# zxuno.net
KiCad netlist of a schematic drawn in Altium Designer
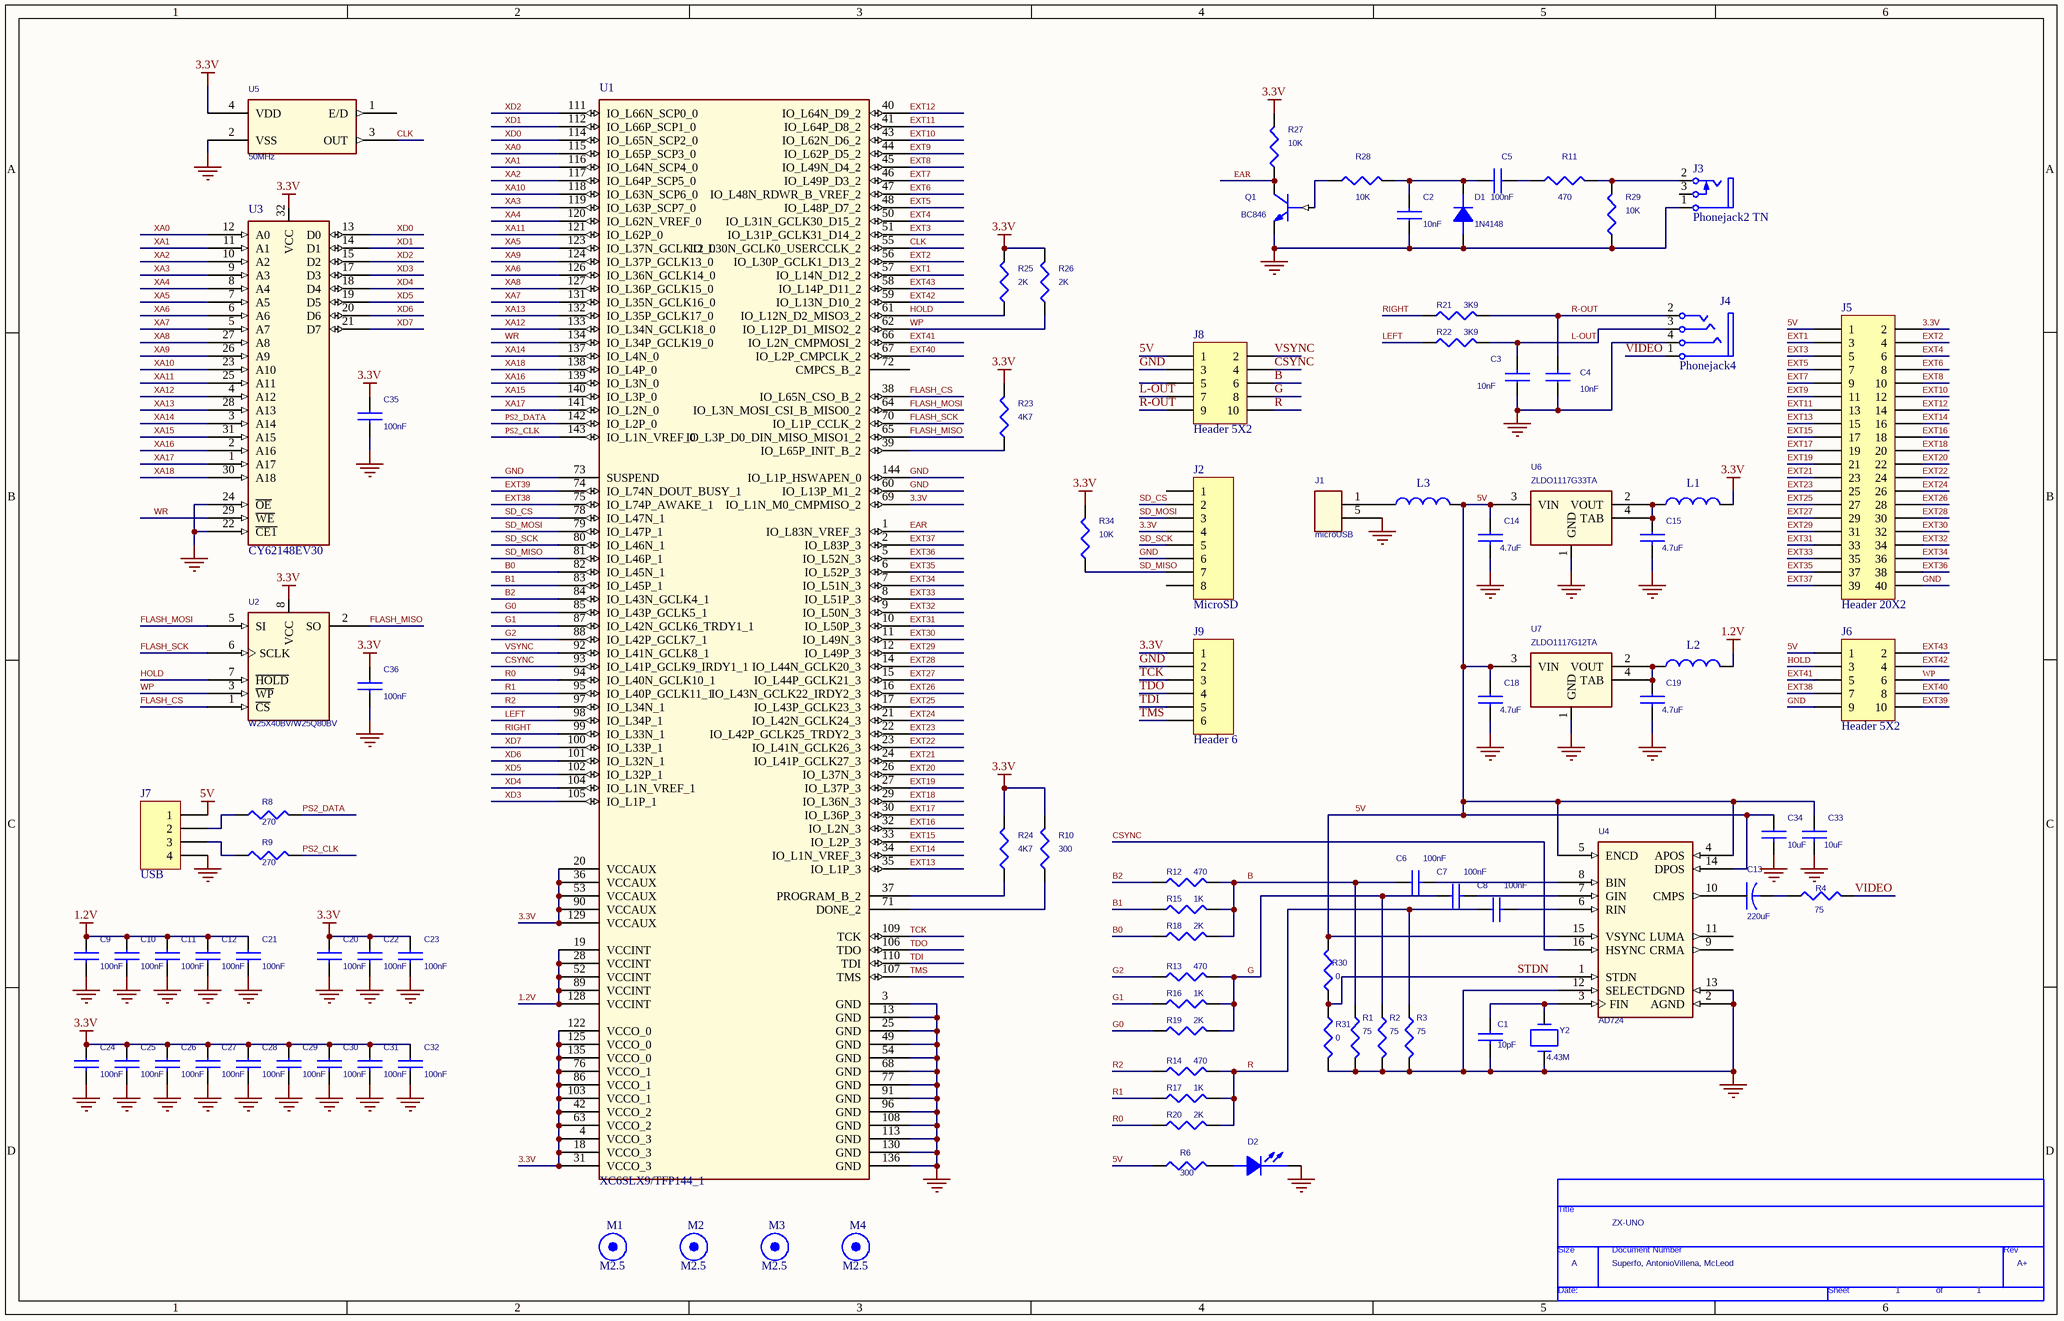
[diagram p0: zxuno.SchDoc]

(export (version "E")
  (design (tool "Eeschema 10.0.6"))
  (components
    (comp (ref "*")
      (value "TitleBlock0")
      (fields
        (field (name "PAGE COUNT") "1")
        (field (name "PAGE NUMBER") "1")
        (field (name "PAGE SIZE") "A")
        (field (name "TITLE") "ZX-UNO")
        (field (name "REVCODE") "A+")
        (field (name "DOC") "Superfo, AntonioVillena, McLeod")
      )
      (libsource (lib "*") (part "TitleBlock0"))
    )
    (comp (ref "C1") (value "10pF") (libsource (lib "*") (part "CAP NP_Dup1")))
    (comp (ref "C2") (value "10nF") (libsource (lib "*") (part "CAP NP_Dup1")))
    (comp (ref "C3") (value "10nF") (libsource (lib "*") (part "CAP NP_Dup1")))
    (comp (ref "C4") (value "10nF") (libsource (lib "*") (part "CAP NP_Dup1")))
    (comp (ref "C5") (value "100nF") (libsource (lib "*") (part "CAP NP_Dup1")))
    (comp (ref "C6") (value "100nF") (libsource (lib "*") (part "CAP NP_Dup1")))
    (comp (ref "C7") (value "100nF") (libsource (lib "*") (part "CAP NP_Dup1")))
    (comp (ref "C8") (value "100nF") (libsource (lib "*") (part "CAP NP_Dup1")))
    (comp (ref "C9") (value "100nF") (libsource (lib "*") (part "CAP NP")))
    (comp (ref "C10") (value "100nF") (libsource (lib "*") (part "CAP NP")))
    (comp (ref "C11") (value "100nF") (libsource (lib "*") (part "CAP NP")))
    (comp (ref "C12") (value "100nF") (libsource (lib "*") (part "CAP NP")))
    (comp (ref "C13") (value "220uF") (libsource (lib "*") (part "CAP")))
    (comp (ref "C14") (value "4.7uF") (libsource (lib "*") (part "CAP NP")))
    (comp (ref "C15") (value "4.7uF") (libsource (lib "*") (part "CAP NP")))
    (comp (ref "C18") (value "4.7uF") (libsource (lib "*") (part "CAP NP")))
    (comp (ref "C19") (value "4.7uF") (libsource (lib "*") (part "CAP NP")))
    (comp (ref "C20") (value "100nF") (libsource (lib "*") (part "CAP NP")))
    (comp (ref "C21") (value "100nF") (libsource (lib "*") (part "CAP NP")))
    (comp (ref "C22") (value "100nF") (libsource (lib "*") (part "CAP NP")))
    (comp (ref "C23") (value "100nF") (libsource (lib "*") (part "CAP NP")))
    (comp (ref "C24") (value "100nF") (libsource (lib "*") (part "CAP NP")))
    (comp (ref "C25") (value "100nF") (libsource (lib "*") (part "CAP NP")))
    (comp (ref "C26") (value "100nF") (libsource (lib "*") (part "CAP NP")))
    (comp (ref "C27") (value "100nF") (libsource (lib "*") (part "CAP NP")))
    (comp (ref "C28") (value "100nF") (libsource (lib "*") (part "CAP NP")))
    (comp (ref "C29") (value "100nF") (libsource (lib "*") (part "CAP NP")))
    (comp (ref "C30") (value "100nF") (libsource (lib "*") (part "CAP NP")))
    (comp (ref "C31") (value "100nF") (libsource (lib "*") (part "CAP NP")))
    (comp (ref "C32") (value "100nF") (libsource (lib "*") (part "CAP NP")))
    (comp (ref "C33") (value "10uF") (libsource (lib "*") (part "CAP NP")))
    (comp (ref "C34") (value "10uF") (libsource (lib "*") (part "CAP NP")))
    (comp (ref "C35") (value "100nF") (libsource (lib "*") (part "CAP NP")))
    (comp (ref "C36") (value "100nF") (libsource (lib "*") (part "CAP NP")))
    (comp (ref "D1") (value "1N4148") (libsource (lib "*") (part "DIODE")))
    (comp (ref "D2") (value "LED") (libsource (lib "*") (part "LED")))
    (comp (ref "J1") (value "microUSB") (libsource (lib "*") (part "CON2_0")))
    (comp (ref "J2")
      (value "MicroSD")
      (footprint "SD HR1941CT-ND")
      (description "Header, 8-Pin")
      (fields (field (name "PUBLISHER") "Altium Limited"))
      (libsource (lib "Miscellaneous Connectors") (part "Header 8"))
    )
    (comp (ref "J3")
      (value "Phonejack2 TN")
      (footprint "AUDIO  JACK MJ-2523-SMT")
      (description "Jack Socket, 3.5mm, Thru-Hole, Vertical, 2-Conductor with Tip closed")
      (fields (field (name "PUBLISHER") "Altium Limited"))
      (libsource (lib "Retro Computer") (part "Phonejack2 TN"))
    )
    (comp (ref "J4")
      (value "Phonejack4")
      (footprint "AUDIO  JACK SJ-43514-SMT")
      (description "Jack Socket, 3.5mm, Thru-Hole, Right Angle, 4-Conductor")
      (fields (field (name "PUBLISHER") "Altium Limited"))
      (libsource (lib "Retro Computer") (part "Phonejack4"))
    )
    (comp (ref "J5")
      (value "Header 20X2")
      (footprint "HDR2X20")
      (description "Header, 20-Pin, Dual row")
      (fields (field (name "PUBLISHER") "Altium Limited"))
      (libsource (lib "Miscellaneous Connectors") (part "Header 20X2"))
    )
    (comp (ref "J6")
      (value "Header 5X2")
      (footprint "HDR2X5")
      (description "Header, 5-Pin, Dual row")
      (fields (field (name "PUBLISHER") "Altium Limited"))
      (libsource (lib "Miscellaneous Connectors") (part "Header 5X2"))
    )
    (comp (ref "J7")
      (value "USB")
      (footprint "USB A")
      (description "Header, 4-Pin")
      (fields (field (name "PUBLISHER") "Altium Limited"))
      (libsource (lib "Miscellaneous Connectors") (part "Header 4"))
    )
    (comp (ref "J8")
      (value "Header 5X2")
      (footprint "HDR2X5")
      (description "Header, 5-Pin, Dual row")
      (fields (field (name "PUBLISHER") "Altium Limited"))
      (libsource (lib "Miscellaneous Connectors") (part "Header 5X2"))
    )
    (comp (ref "J9")
      (value "Header 6")
      (footprint "HDR1X6")
      (description "Header, 6-Pin")
      (fields (field (name "PUBLISHER") "Altium Limited"))
      (libsource (lib "Miscellaneous Connectors") (part "Header 6"))
    )
    (comp (ref "L1")
      (value "Inductor")
      (footprint "SM/L_0805")
      (fields (field (name "PUBLISHER") "Altium Limited"))
      (libsource (lib "Miscellaneous Devices") (part "Inductor"))
    )
    (comp (ref "L2")
      (value "Inductor")
      (footprint "SM/L_0805")
      (fields (field (name "PUBLISHER") "Altium Limited"))
      (libsource (lib "Miscellaneous Devices") (part "Inductor"))
    )
    (comp (ref "L3")
      (value "Inductor")
      (footprint "SM/L_0805")
      (fields (field (name "PUBLISHER") "Altium Limited"))
      (libsource (lib "Miscellaneous Devices") (part "Inductor"))
    )
    (comp (ref "M1") (value "M2.5") (footprint "M2.5") (libsource (lib "Misc Devices 2") (part "M2.5")))
    (comp (ref "M2") (value "M2.5") (footprint "M2.5") (libsource (lib "Misc Devices 2") (part "M2.5")))
    (comp (ref "M3") (value "M2.5") (footprint "M2.5") (libsource (lib "Misc Devices 2") (part "M2.5")))
    (comp (ref "M4") (value "M2.5") (footprint "M2.5") (libsource (lib "Misc Devices 2") (part "M2.5")))
    (comp (ref "Q1") (value "BC846") (libsource (lib "*") (part "BC547")))
    (comp (ref "R1") (value "75") (libsource (lib "*") (part "R")))
    (comp (ref "R2") (value "75") (libsource (lib "*") (part "R")))
    (comp (ref "R3") (value "75") (libsource (lib "*") (part "R")))
    (comp (ref "R4") (value "75") (libsource (lib "*") (part "R")))
    (comp (ref "R6") (value "300") (libsource (lib "*") (part "R")))
    (comp (ref "R8") (value "270") (libsource (lib "*") (part "R")))
    (comp (ref "R9") (value "270") (libsource (lib "*") (part "R")))
    (comp (ref "R10") (value "300") (libsource (lib "*") (part "R")))
    (comp (ref "R11") (value "470") (libsource (lib "*") (part "R")))
    (comp (ref "R12") (value "470") (libsource (lib "*") (part "R")))
    (comp (ref "R13") (value "470") (libsource (lib "*") (part "R")))
    (comp (ref "R14") (value "470") (libsource (lib "*") (part "R")))
    (comp (ref "R15") (value "1K") (libsource (lib "*") (part "R")))
    (comp (ref "R16") (value "1K") (libsource (lib "*") (part "R")))
    (comp (ref "R17") (value "1K") (libsource (lib "*") (part "R")))
    (comp (ref "R18") (value "2K") (libsource (lib "*") (part "R")))
    (comp (ref "R19") (value "2K") (libsource (lib "*") (part "R")))
    (comp (ref "R20") (value "2K") (libsource (lib "*") (part "R")))
    (comp (ref "R21") (value "3K9") (libsource (lib "*") (part "R")))
    (comp (ref "R22") (value "3K9") (libsource (lib "*") (part "R")))
    (comp (ref "R23") (value "4K7") (libsource (lib "*") (part "R")))
    (comp (ref "R24") (value "4K7") (libsource (lib "*") (part "R")))
    (comp (ref "R25") (value "2K") (libsource (lib "*") (part "R")))
    (comp (ref "R26") (value "2K") (libsource (lib "*") (part "R")))
    (comp (ref "R27") (value "10K") (libsource (lib "*") (part "R")))
    (comp (ref "R28") (value "10K") (libsource (lib "*") (part "R")))
    (comp (ref "R29") (value "10K") (libsource (lib "*") (part "R")))
    (comp (ref "R30") (value "0") (libsource (lib "*") (part "R")))
    (comp (ref "R31") (value "0") (libsource (lib "*") (part "R")))
    (comp (ref "R34") (value "10K") (libsource (lib "*") (part "R")))
    (comp (ref "U1")
      (value "XC6SLX9/TFP144_1")
      (libsource (lib "ZX_UNO_0_13_Library") (part "XC6SLX9/TFP144_1"))
    )
    (comp (ref "U2") (value "W25X40BV/W25Q80BV") (libsource (lib "*") (part "AT45DB011/SOIC_3")))
    (comp (ref "U3") (value "CY62148EV30") (libsource (lib "ZX_UNO_0_13_Library") (part "CY62128/SOIC_3")))
    (comp (ref "U4") (value "AD724") (libsource (lib "*") (part "AD724")))
    (comp (ref "U5") (value "50MHz") (libsource (lib "*") (part "CS-403/TO_0")))
    (comp (ref "U6")
      (value "ZLDO1117G33TA")
      (footprint "SM/SOT223")
      (libsource (lib "*") (part "REGULATOR-1_0"))
    )
    (comp (ref "U7")
      (value "ZLDO1117G12TA")
      (footprint "SM/SOT223")
      (libsource (lib "*") (part "REGULATOR-1_0"))
    )
    (comp (ref "Y2") (value "4.43M") (libsource (lib "*") (part "CRYSTAL")))
  )
  (nets
    (net (code "1") (name "/B") (class "Default")
      (node (ref "C6") (pin "1") (pinfunction "1_1") (pintype "passive"))
      (node (ref "J8") (pin "6") (pinfunction "6_6") (pintype "passive"))
      (node (ref "R1") (pin "1") (pinfunction "1_1") (pintype "passive"))
      (node (ref "R12") (pin "2") (pinfunction "2_2") (pintype "passive"))
      (node (ref "R15") (pin "2") (pinfunction "2_2") (pintype "passive"))
      (node (ref "R18") (pin "2") (pinfunction "2_2") (pintype "passive"))
    )
    (net (code "2") (name "/B0") (class "Default")
      (node (ref "R18") (pin "1") (pinfunction "1_1") (pintype "passive"))
      (node (ref "U1") (pin "82") (pinfunction "IO_L45N_1_82") (pintype "bidirectional"))
    )
    (net (code "3") (name "/B1") (class "Default")
      (node (ref "R15") (pin "1") (pinfunction "1_1") (pintype "passive"))
      (node (ref "U1") (pin "83") (pinfunction "IO_L45P_1_83") (pintype "bidirectional"))
    )
    (net (code "4") (name "/B2") (class "Default")
      (node (ref "R12") (pin "1") (pinfunction "1_1") (pintype "passive"))
      (node (ref "U1") (pin "84") (pinfunction "IO_L43N_GCLK4_1_84") (pintype "bidirectional"))
    )
    (net (code "5") (name "/CLK") (class "Default")
      (node (ref "U1") (pin "55") (pinfunction "IO_L30N_GCLK0_USERCCLK_2_55") (pintype "bidirectional"))
      (node (ref "U5") (pin "3") (pinfunction "OUT_3") (pintype "output"))
    )
    (net (code "6") (name "/CSYNC") (class "Default")
      (node (ref "J8") (pin "4") (pinfunction "4_4") (pintype "passive"))
      (node (ref "U1") (pin "93") (pinfunction "IO_L41P_GCLK9_IRDY1_1_93") (pintype "bidirectional"))
      (node (ref "U4") (pin "16") (pinfunction "HSYNC_16") (pintype "input"))
    )
    (net (code "7") (name "/EAR") (class "Default")
      (node (ref "Q1") (pin "1") (pinfunction "COLLECTOR_1") (pintype "passive"))
      (node (ref "R27") (pin "2") (pinfunction "2_2") (pintype "passive"))
      (node (ref "U1") (pin "1") (pinfunction "IO_L83N_VREF_3_1") (pintype "bidirectional"))
    )
    (net (code "8") (name "/EXT1") (class "Default")
      (node (ref "J5") (pin "3") (pinfunction "3_3") (pintype "passive"))
      (node (ref "U1") (pin "57") (pinfunction "IO_L14N_D12_2_57") (pintype "bidirectional"))
    )
    (net (code "9") (name "/EXT2") (class "Default")
      (node (ref "J5") (pin "4") (pinfunction "4_4") (pintype "passive"))
      (node (ref "U1") (pin "56") (pinfunction "IO_L30P_GCLK1_D13_2_56") (pintype "bidirectional"))
    )
    (net (code "10") (name "/EXT3") (class "Default")
      (node (ref "J5") (pin "5") (pinfunction "5_5") (pintype "passive"))
      (node (ref "U1") (pin "51") (pinfunction "IO_L31P_GCLK31_D14_2_51") (pintype "bidirectional"))
    )
    (net (code "11") (name "/EXT4") (class "Default")
      (node (ref "J5") (pin "6") (pinfunction "6_6") (pintype "passive"))
      (node (ref "U1") (pin "50") (pinfunction "IO_L31N_GCLK30_D15_2_50") (pintype "bidirectional"))
    )
    (net (code "12") (name "/EXT5") (class "Default")
      (node (ref "J5") (pin "7") (pinfunction "7_7") (pintype "passive"))
      (node (ref "U1") (pin "48") (pinfunction "IO_L48P_D7_2_48") (pintype "bidirectional"))
    )
    (net (code "13") (name "/EXT6") (class "Default")
      (node (ref "J5") (pin "8") (pinfunction "8_8") (pintype "passive"))
      (node (ref "U1") (pin "47") (pinfunction "IO_L48N_RDWR_B_VREF_2_47") (pintype "bidirectional"))
    )
    (net (code "14") (name "/EXT7") (class "Default")
      (node (ref "J5") (pin "9") (pinfunction "9_9") (pintype "passive"))
      (node (ref "U1") (pin "46") (pinfunction "IO_L49P_D3_2_46") (pintype "bidirectional"))
    )
    (net (code "15") (name "/EXT8") (class "Default")
      (node (ref "J5") (pin "10") (pinfunction "10_10") (pintype "passive"))
      (node (ref "U1") (pin "45") (pinfunction "IO_L49N_D4_2_45") (pintype "bidirectional"))
    )
    (net (code "16") (name "/EXT9") (class "Default")
      (node (ref "J5") (pin "11") (pinfunction "11_11") (pintype "passive"))
      (node (ref "U1") (pin "44") (pinfunction "IO_L62P_D5_2_44") (pintype "bidirectional"))
    )
    (net (code "17") (name "/EXT10") (class "Default")
      (node (ref "J5") (pin "12") (pinfunction "12_12") (pintype "passive"))
      (node (ref "U1") (pin "43") (pinfunction "IO_L62N_D6_2_43") (pintype "bidirectional"))
    )
    (net (code "18") (name "/EXT11") (class "Default")
      (node (ref "J5") (pin "13") (pinfunction "13_13") (pintype "passive"))
      (node (ref "U1") (pin "41") (pinfunction "IO_L64P_D8_2_41") (pintype "bidirectional"))
    )
    (net (code "19") (name "/EXT12") (class "Default")
      (node (ref "J5") (pin "14") (pinfunction "14_14") (pintype "passive"))
      (node (ref "U1") (pin "40") (pinfunction "IO_L64N_D9_2_40") (pintype "bidirectional"))
    )
    (net (code "20") (name "/EXT13") (class "Default")
      (node (ref "J5") (pin "15") (pinfunction "15_15") (pintype "passive"))
      (node (ref "U1") (pin "35") (pinfunction "IO_L1P_3_35") (pintype "bidirectional"))
    )
    (net (code "21") (name "/EXT14") (class "Default")
      (node (ref "J5") (pin "16") (pinfunction "16_16") (pintype "passive"))
      (node (ref "U1") (pin "34") (pinfunction "IO_L1N_VREF_3_34") (pintype "bidirectional"))
    )
    (net (code "22") (name "/EXT15") (class "Default")
      (node (ref "J5") (pin "17") (pinfunction "17_17") (pintype "passive"))
      (node (ref "U1") (pin "33") (pinfunction "IO_L2P_3_33") (pintype "bidirectional"))
    )
    (net (code "23") (name "/EXT16") (class "Default")
      (node (ref "J5") (pin "18") (pinfunction "18_18") (pintype "passive"))
      (node (ref "U1") (pin "32") (pinfunction "IO_L2N_3_32") (pintype "bidirectional"))
    )
    (net (code "24") (name "/EXT17") (class "Default")
      (node (ref "J5") (pin "19") (pinfunction "19_19") (pintype "passive"))
      (node (ref "U1") (pin "30") (pinfunction "IO_L36P_3_30") (pintype "bidirectional"))
    )
    (net (code "25") (name "/EXT18") (class "Default")
      (node (ref "J5") (pin "20") (pinfunction "20_20") (pintype "passive"))
      (node (ref "U1") (pin "29") (pinfunction "IO_L36N_3_29") (pintype "bidirectional"))
    )
    (net (code "26") (name "/EXT19") (class "Default")
      (node (ref "J5") (pin "21") (pinfunction "21_21") (pintype "passive"))
      (node (ref "U1") (pin "27") (pinfunction "IO_L37P_3_27") (pintype "bidirectional"))
    )
    (net (code "27") (name "/EXT20") (class "Default")
      (node (ref "J5") (pin "22") (pinfunction "22_22") (pintype "passive"))
      (node (ref "U1") (pin "26") (pinfunction "IO_L37N_3_26") (pintype "bidirectional"))
    )
    (net (code "28") (name "/EXT21") (class "Default")
      (node (ref "J5") (pin "23") (pinfunction "23_23") (pintype "passive"))
      (node (ref "U1") (pin "24") (pinfunction "IO_L41P_GCLK27_3_24") (pintype "bidirectional"))
    )
    (net (code "29") (name "/EXT22") (class "Default")
      (node (ref "J5") (pin "24") (pinfunction "24_24") (pintype "passive"))
      (node (ref "U1") (pin "23") (pinfunction "IO_L41N_GCLK26_3_23") (pintype "bidirectional"))
    )
    (net (code "30") (name "/EXT23") (class "Default")
      (node (ref "J5") (pin "25") (pinfunction "25_25") (pintype "passive"))
      (node (ref "U1") (pin "22") (pinfunction "IO_L42P_GCLK25_TRDY2_3_22") (pintype "bidirectional"))
    )
    (net (code "31") (name "/EXT24") (class "Default")
      (node (ref "J5") (pin "26") (pinfunction "26_26") (pintype "passive"))
      (node (ref "U1") (pin "21") (pinfunction "IO_L42N_GCLK24_3_21") (pintype "bidirectional"))
    )
    (net (code "32") (name "/EXT25") (class "Default")
      (node (ref "J5") (pin "27") (pinfunction "27_27") (pintype "passive"))
      (node (ref "U1") (pin "17") (pinfunction "IO_L43P_GCLK23_3_17") (pintype "bidirectional"))
    )
    (net (code "33") (name "/EXT26") (class "Default")
      (node (ref "J5") (pin "28") (pinfunction "28_28") (pintype "passive"))
      (node (ref "U1") (pin "16") (pinfunction "IO_L43N_GCLK22_IRDY2_3_16") (pintype "bidirectional"))
    )
    (net (code "34") (name "/EXT27") (class "Default")
      (node (ref "J5") (pin "29") (pinfunction "29_29") (pintype "passive"))
      (node (ref "U1") (pin "15") (pinfunction "IO_L44P_GCLK21_3_15") (pintype "bidirectional"))
    )
    (net (code "35") (name "/EXT28") (class "Default")
      (node (ref "J5") (pin "30") (pinfunction "30_30") (pintype "passive"))
      (node (ref "U1") (pin "14") (pinfunction "IO_L44N_GCLK20_3_14") (pintype "bidirectional"))
    )
    (net (code "36") (name "/EXT29") (class "Default")
      (node (ref "J5") (pin "31") (pinfunction "31_31") (pintype "passive"))
      (node (ref "U1") (pin "12") (pinfunction "IO_L49P_3_12") (pintype "bidirectional"))
    )
    (net (code "37") (name "/EXT30") (class "Default")
      (node (ref "J5") (pin "32") (pinfunction "32_32") (pintype "passive"))
      (node (ref "U1") (pin "11") (pinfunction "IO_L49N_3_11") (pintype "bidirectional"))
    )
    (net (code "38") (name "/EXT31") (class "Default")
      (node (ref "J5") (pin "33") (pinfunction "33_33") (pintype "passive"))
      (node (ref "U1") (pin "10") (pinfunction "IO_L50P_3_10") (pintype "bidirectional"))
    )
    (net (code "39") (name "/EXT32") (class "Default")
      (node (ref "J5") (pin "34") (pinfunction "34_34") (pintype "passive"))
      (node (ref "U1") (pin "9") (pinfunction "IO_L50N_3_9") (pintype "bidirectional"))
    )
    (net (code "40") (name "/EXT33") (class "Default")
      (node (ref "J5") (pin "35") (pinfunction "35_35") (pintype "passive"))
      (node (ref "U1") (pin "8") (pinfunction "IO_L51P_3_8") (pintype "bidirectional"))
    )
    (net (code "41") (name "/EXT34") (class "Default")
      (node (ref "J5") (pin "36") (pinfunction "36_36") (pintype "passive"))
      (node (ref "U1") (pin "7") (pinfunction "IO_L51N_3_7") (pintype "bidirectional"))
    )
    (net (code "42") (name "/EXT35") (class "Default")
      (node (ref "J5") (pin "37") (pinfunction "37_37") (pintype "passive"))
      (node (ref "U1") (pin "6") (pinfunction "IO_L52P_3_6") (pintype "bidirectional"))
    )
    (net (code "43") (name "/EXT36") (class "Default")
      (node (ref "J5") (pin "38") (pinfunction "38_38") (pintype "passive"))
      (node (ref "U1") (pin "5") (pinfunction "IO_L52N_3_5") (pintype "bidirectional"))
    )
    (net (code "44") (name "/EXT37") (class "Default")
      (node (ref "J5") (pin "39") (pinfunction "39_39") (pintype "passive"))
      (node (ref "U1") (pin "2") (pinfunction "IO_L83P_3_2") (pintype "bidirectional"))
    )
    (net (code "45") (name "/EXT38") (class "Default")
      (node (ref "J6") (pin "7") (pinfunction "7_7") (pintype "passive"))
      (node (ref "U1") (pin "75") (pinfunction "IO_L74P_AWAKE_1_75") (pintype "bidirectional"))
    )
    (net (code "46") (name "/EXT39") (class "Default")
      (node (ref "J6") (pin "10") (pinfunction "10_10") (pintype "passive"))
      (node (ref "U1") (pin "74") (pinfunction "IO_L74N_DOUT_BUSY_1_74") (pintype "bidirectional"))
    )
    (net (code "47") (name "/EXT40") (class "Default")
      (node (ref "J6") (pin "8") (pinfunction "8_8") (pintype "passive"))
      (node (ref "U1") (pin "67") (pinfunction "IO_L2P_CMPCLK_2_67") (pintype "bidirectional"))
    )
    (net (code "48") (name "/EXT41") (class "Default")
      (node (ref "J6") (pin "5") (pinfunction "5_5") (pintype "passive"))
      (node (ref "U1") (pin "66") (pinfunction "IO_L2N_CMPMOSI_2_66") (pintype "bidirectional"))
    )
    (net (code "49") (name "/EXT42") (class "Default")
      (node (ref "J6") (pin "4") (pinfunction "4_4") (pintype "passive"))
      (node (ref "U1") (pin "59") (pinfunction "IO_L13N_D10_2_59") (pintype "bidirectional"))
    )
    (net (code "50") (name "/EXT43") (class "Default")
      (node (ref "J6") (pin "2") (pinfunction "2_2") (pintype "passive"))
      (node (ref "U1") (pin "58") (pinfunction "IO_L14P_D11_2_58") (pintype "bidirectional"))
    )
    (net (code "51") (name "/FLASH_CS") (class "Default")
      (node (ref "U1") (pin "38") (pinfunction "IO_L65N_CSO_B_2_38") (pintype "bidirectional"))
      (node (ref "U2") (pin "1") (pinfunction "~{CS}_1") (pintype "input"))
    )
    (net (code "52") (name "/FLASH_MISO") (class "Default")
      (node (ref "U1") (pin "65") (pinfunction "IO_L3P_D0_DIN_MISO_MISO1_2_65") (pintype "bidirectional"))
      (node (ref "U2") (pin "2") (pinfunction "SO_2") (pintype "tri_state"))
    )
    (net (code "53") (name "/FLASH_MOSI") (class "Default")
      (node (ref "U1") (pin "64") (pinfunction "IO_L3N_MOSI_CSI_B_MISO0_2_64") (pintype "bidirectional"))
      (node (ref "U2") (pin "5") (pinfunction "SI_5") (pintype "input"))
    )
    (net (code "54") (name "/FLASH_SCK") (class "Default")
      (node (ref "U1") (pin "70") (pinfunction "IO_L1P_CCLK_2_70") (pintype "bidirectional"))
      (node (ref "U2") (pin "6") (pinfunction "SCLK_6") (pintype "input"))
    )
    (net (code "55") (name "/G") (class "Default")
      (node (ref "C7") (pin "1") (pinfunction "1_1") (pintype "passive"))
      (node (ref "J8") (pin "8") (pinfunction "8_8") (pintype "passive"))
      (node (ref "R13") (pin "2") (pinfunction "2_2") (pintype "passive"))
      (node (ref "R16") (pin "2") (pinfunction "2_2") (pintype "passive"))
      (node (ref "R19") (pin "2") (pinfunction "2_2") (pintype "passive"))
      (node (ref "R2") (pin "1") (pinfunction "1_1") (pintype "passive"))
    )
    (net (code "56") (name "/G0") (class "Default")
      (node (ref "R19") (pin "1") (pinfunction "1_1") (pintype "passive"))
      (node (ref "U1") (pin "85") (pinfunction "IO_L43P_GCLK5_1_85") (pintype "bidirectional"))
    )
    (net (code "57") (name "/G1") (class "Default")
      (node (ref "R16") (pin "1") (pinfunction "1_1") (pintype "passive"))
      (node (ref "U1") (pin "87") (pinfunction "IO_L42N_GCLK6_TRDY1_1_87") (pintype "bidirectional"))
    )
    (net (code "58") (name "/G2") (class "Default")
      (node (ref "R13") (pin "1") (pinfunction "1_1") (pintype "passive"))
      (node (ref "U1") (pin "88") (pinfunction "IO_L42P_GCLK7_1_88") (pintype "bidirectional"))
    )
    (net (code "59") (name "/HOLD") (class "Default")
      (node (ref "J6") (pin "3") (pinfunction "3_3") (pintype "passive"))
      (node (ref "R25") (pin "1") (pinfunction "1_1") (pintype "passive"))
      (node (ref "U1") (pin "61") (pinfunction "IO_L12N_D2_MISO3_2_61") (pintype "bidirectional"))
      (node (ref "U2") (pin "7") (pinfunction "~{HOLD}_7") (pintype "input"))
    )
    (net (code "60") (name "/L-OUT") (class "Default")
      (node (ref "C3") (pin "2") (pinfunction "2_2") (pintype "passive"))
      (node (ref "J4") (pin "3") (pinfunction "RN_3") (pintype "passive"))
      (node (ref "J8") (pin "7") (pinfunction "7_7") (pintype "passive"))
      (node (ref "R22") (pin "2") (pinfunction "2_2") (pintype "passive"))
    )
    (net (code "61") (name "/LEFT") (class "Default")
      (node (ref "R22") (pin "1") (pinfunction "1_1") (pintype "passive"))
      (node (ref "U1") (pin "98") (pinfunction "IO_L34P_1_98") (pintype "bidirectional"))
    )
    (net (code "62") (name "/PS2_CLK") (class "Default")
      (node (ref "R9") (pin "2") (pinfunction "2_2") (pintype "passive"))
      (node (ref "U1") (pin "143") (pinfunction "IO_L1N_VREF_0_143") (pintype "bidirectional"))
    )
    (net (code "63") (name "/PS2_DATA") (class "Default")
      (node (ref "R8") (pin "2") (pinfunction "2_2") (pintype "passive"))
      (node (ref "U1") (pin "142") (pinfunction "IO_L2P_0_142") (pintype "bidirectional"))
    )
    (net (code "64") (name "/R") (class "Default")
      (node (ref "C8") (pin "1") (pinfunction "1_1") (pintype "passive"))
      (node (ref "J8") (pin "10") (pinfunction "10_10") (pintype "passive"))
      (node (ref "R14") (pin "2") (pinfunction "2_2") (pintype "passive"))
      (node (ref "R17") (pin "2") (pinfunction "2_2") (pintype "passive"))
      (node (ref "R20") (pin "2") (pinfunction "2_2") (pintype "passive"))
      (node (ref "R3") (pin "1") (pinfunction "1_1") (pintype "passive"))
    )
    (net (code "65") (name "/R-OUT") (class "Default")
      (node (ref "C4") (pin "2") (pinfunction "2_2") (pintype "passive"))
      (node (ref "J4") (pin "2") (pinfunction "T_2") (pintype "passive"))
      (node (ref "J8") (pin "9") (pinfunction "9_9") (pintype "passive"))
      (node (ref "R21") (pin "2") (pinfunction "2_2") (pintype "passive"))
    )
    (net (code "66") (name "/R0") (class "Default")
      (node (ref "R20") (pin "1") (pinfunction "1_1") (pintype "passive"))
      (node (ref "U1") (pin "94") (pinfunction "IO_L40N_GCLK10_1_94") (pintype "bidirectional"))
    )
    (net (code "67") (name "/R1") (class "Default")
      (node (ref "R17") (pin "1") (pinfunction "1_1") (pintype "passive"))
      (node (ref "U1") (pin "95") (pinfunction "IO_L40P_GCLK11_1_95") (pintype "bidirectional"))
    )
    (net (code "68") (name "/R2") (class "Default")
      (node (ref "R14") (pin "1") (pinfunction "1_1") (pintype "passive"))
      (node (ref "U1") (pin "97") (pinfunction "IO_L34N_1_97") (pintype "bidirectional"))
    )
    (net (code "69") (name "/RIGHT") (class "Default")
      (node (ref "R21") (pin "1") (pinfunction "1_1") (pintype "passive"))
      (node (ref "U1") (pin "99") (pinfunction "IO_L33N_1_99") (pintype "bidirectional"))
    )
    (net (code "70") (name "/SD_CS") (class "Default")
      (node (ref "J2") (pin "2") (pinfunction "2_2") (pintype "passive"))
      (node (ref "U1") (pin "78") (pinfunction "IO_L47N_1_78") (pintype "bidirectional"))
    )
    (net (code "71") (name "/SD_MISO") (class "Default")
      (node (ref "J2") (pin "7") (pinfunction "7_7") (pintype "passive"))
      (node (ref "R34") (pin "1") (pinfunction "1_1") (pintype "passive"))
      (node (ref "U1") (pin "81") (pinfunction "IO_L46P_1_81") (pintype "bidirectional"))
    )
    (net (code "72") (name "/SD_MOSI") (class "Default")
      (node (ref "J2") (pin "3") (pinfunction "3_3") (pintype "passive"))
      (node (ref "U1") (pin "79") (pinfunction "IO_L47P_1_79") (pintype "bidirectional"))
    )
    (net (code "73") (name "/SD_SCK") (class "Default")
      (node (ref "J2") (pin "5") (pinfunction "5_5") (pintype "passive"))
      (node (ref "U1") (pin "80") (pinfunction "IO_L46N_1_80") (pintype "bidirectional"))
    )
    (net (code "74") (name "/STDN") (class "Default")
      (node (ref "R30") (pin "1") (pinfunction "1_1") (pintype "passive"))
      (node (ref "R31") (pin "1") (pinfunction "1_1") (pintype "passive"))
      (node (ref "U4") (pin "1") (pinfunction "STDN_1") (pintype "input"))
    )
    (net (code "75") (name "/TCK") (class "Default")
      (node (ref "J9") (pin "3") (pinfunction "3_3") (pintype "passive"))
      (node (ref "U1") (pin "109") (pinfunction "TCK_109") (pintype "bidirectional"))
    )
    (net (code "76") (name "/TDI") (class "Default")
      (node (ref "J9") (pin "5") (pinfunction "5_5") (pintype "passive"))
      (node (ref "U1") (pin "110") (pinfunction "TDI_110") (pintype "bidirectional"))
    )
    (net (code "77") (name "/TDO") (class "Default")
      (node (ref "J9") (pin "4") (pinfunction "4_4") (pintype "passive"))
      (node (ref "U1") (pin "106") (pinfunction "TDO_106") (pintype "bidirectional"))
    )
    (net (code "78") (name "/TMS") (class "Default")
      (node (ref "J9") (pin "6") (pinfunction "6_6") (pintype "passive"))
      (node (ref "U1") (pin "107") (pinfunction "TMS_107") (pintype "bidirectional"))
    )
    (net (code "79") (name "/VIDEO") (class "Default")
      (node (ref "J4") (pin "1") (pinfunction "S_1") (pintype "passive"))
      (node (ref "R4") (pin "2") (pinfunction "2_2") (pintype "passive"))
    )
    (net (code "80") (name "/VSYNC") (class "Default")
      (node (ref "J8") (pin "2") (pinfunction "2_2") (pintype "passive"))
      (node (ref "U1") (pin "92") (pinfunction "IO_L41N_GCLK8_1_92") (pintype "bidirectional"))
    )
    (net (code "81") (name "/WP") (class "Default")
      (node (ref "J6") (pin "6") (pinfunction "6_6") (pintype "passive"))
      (node (ref "R26") (pin "1") (pinfunction "1_1") (pintype "passive"))
      (node (ref "U1") (pin "62") (pinfunction "IO_L12P_D1_MISO2_2_62") (pintype "bidirectional"))
      (node (ref "U2") (pin "3") (pinfunction "~{WP}_3") (pintype "input"))
    )
    (net (code "82") (name "/WR") (class "Default")
      (node (ref "U1") (pin "134") (pinfunction "IO_L34P_GCLK19_0_134") (pintype "bidirectional"))
      (node (ref "U3") (pin "29") (pinfunction "~{WE}_29") (pintype "input"))
    )
    (net (code "83") (name "/XA0") (class "Default")
      (node (ref "U1") (pin "115") (pinfunction "IO_L65P_SCP3_0_115") (pintype "bidirectional"))
      (node (ref "U3") (pin "12") (pinfunction "A0_12") (pintype "input"))
    )
    (net (code "84") (name "/XA1") (class "Default")
      (node (ref "U1") (pin "116") (pinfunction "IO_L64N_SCP4_0_116") (pintype "bidirectional"))
      (node (ref "U3") (pin "11") (pinfunction "A1_11") (pintype "input"))
    )
    (net (code "85") (name "/XA2") (class "Default")
      (node (ref "U1") (pin "117") (pinfunction "IO_L64P_SCP5_0_117") (pintype "bidirectional"))
      (node (ref "U3") (pin "10") (pinfunction "A2_10") (pintype "input"))
    )
    (net (code "86") (name "/XA3") (class "Default")
      (node (ref "U1") (pin "119") (pinfunction "IO_L63P_SCP7_0_119") (pintype "bidirectional"))
      (node (ref "U3") (pin "9") (pinfunction "A3_9") (pintype "input"))
    )
    (net (code "87") (name "/XA4") (class "Default")
      (node (ref "U1") (pin "120") (pinfunction "IO_L62N_VREF_0_120") (pintype "bidirectional"))
      (node (ref "U3") (pin "8") (pinfunction "A4_8") (pintype "input"))
    )
    (net (code "88") (name "/XA5") (class "Default")
      (node (ref "U1") (pin "123") (pinfunction "IO_L37N_GCLK12_0_123") (pintype "bidirectional"))
      (node (ref "U3") (pin "7") (pinfunction "A5_7") (pintype "input"))
    )
    (net (code "89") (name "/XA6") (class "Default")
      (node (ref "U1") (pin "126") (pinfunction "IO_L36N_GCLK14_0_126") (pintype "bidirectional"))
      (node (ref "U3") (pin "6") (pinfunction "A6_6") (pintype "input"))
    )
    (net (code "90") (name "/XA7") (class "Default")
      (node (ref "U1") (pin "131") (pinfunction "IO_L35N_GCLK16_0_131") (pintype "bidirectional"))
      (node (ref "U3") (pin "5") (pinfunction "A7_5") (pintype "input"))
    )
    (net (code "91") (name "/XA8") (class "Default")
      (node (ref "U1") (pin "127") (pinfunction "IO_L36P_GCLK15_0_127") (pintype "bidirectional"))
      (node (ref "U3") (pin "27") (pinfunction "A8_27") (pintype "input"))
    )
    (net (code "92") (name "/XA9") (class "Default")
      (node (ref "U1") (pin "124") (pinfunction "IO_L37P_GCLK13_0_124") (pintype "bidirectional"))
      (node (ref "U3") (pin "26") (pinfunction "A9_26") (pintype "input"))
    )
    (net (code "93") (name "/XA10") (class "Default")
      (node (ref "U1") (pin "118") (pinfunction "IO_L63N_SCP6_0_118") (pintype "bidirectional"))
      (node (ref "U3") (pin "23") (pinfunction "A10_23") (pintype "input"))
    )
    (net (code "94") (name "/XA11") (class "Default")
      (node (ref "U1") (pin "121") (pinfunction "IO_L62P_0_121") (pintype "bidirectional"))
      (node (ref "U3") (pin "25") (pinfunction "A11_25") (pintype "input"))
    )
    (net (code "95") (name "/XA12") (class "Default")
      (node (ref "U1") (pin "133") (pinfunction "IO_L34N_GCLK18_0_133") (pintype "bidirectional"))
      (node (ref "U3") (pin "4") (pinfunction "A12_4") (pintype "input"))
    )
    (net (code "96") (name "/XA13") (class "Default")
      (node (ref "U1") (pin "132") (pinfunction "IO_L35P_GCLK17_0_132") (pintype "bidirectional"))
      (node (ref "U3") (pin "28") (pinfunction "A13_28") (pintype "input"))
    )
    (net (code "97") (name "/XA14") (class "Default")
      (node (ref "U1") (pin "137") (pinfunction "IO_L4N_0_137") (pintype "bidirectional"))
      (node (ref "U3") (pin "3") (pinfunction "A14_3") (pintype "input"))
    )
    (net (code "98") (name "/XA15") (class "Default")
      (node (ref "U1") (pin "140") (pinfunction "IO_L3P_0_140") (pintype "bidirectional"))
      (node (ref "U3") (pin "31") (pinfunction "A15_31") (pintype "input"))
    )
    (net (code "99") (name "/XA16") (class "Default")
      (node (ref "U1") (pin "139") (pinfunction "IO_L3N_0_139") (pintype "bidirectional"))
      (node (ref "U3") (pin "2") (pinfunction "A16_2") (pintype "input"))
    )
    (net (code "100") (name "/XA17") (class "Default")
      (node (ref "U1") (pin "141") (pinfunction "IO_L2N_0_141") (pintype "bidirectional"))
      (node (ref "U3") (pin "1") (pinfunction "A17_1") (pintype "input"))
    )
    (net (code "101") (name "/XA18") (class "Default")
      (node (ref "U1") (pin "138") (pinfunction "IO_L4P_0_138") (pintype "bidirectional"))
      (node (ref "U3") (pin "30") (pinfunction "A18_30") (pintype "input"))
    )
    (net (code "102") (name "/XD0") (class "Default")
      (node (ref "U1") (pin "114") (pinfunction "IO_L65N_SCP2_0_114") (pintype "bidirectional"))
      (node (ref "U3") (pin "13") (pinfunction "D0_13") (pintype "bidirectional"))
    )
    (net (code "103") (name "/XD1") (class "Default")
      (node (ref "U1") (pin "112") (pinfunction "IO_L66P_SCP1_0_112") (pintype "bidirectional"))
      (node (ref "U3") (pin "14") (pinfunction "D1_14") (pintype "bidirectional"))
    )
    (net (code "104") (name "/XD2") (class "Default")
      (node (ref "U1") (pin "111") (pinfunction "IO_L66N_SCP0_0_111") (pintype "bidirectional"))
      (node (ref "U3") (pin "15") (pinfunction "D2_15") (pintype "bidirectional"))
    )
    (net (code "105") (name "/XD3") (class "Default")
      (node (ref "U1") (pin "105") (pinfunction "IO_L1P_1_105") (pintype "bidirectional"))
      (node (ref "U3") (pin "17") (pinfunction "D3_17") (pintype "bidirectional"))
    )
    (net (code "106") (name "/XD4") (class "Default")
      (node (ref "U1") (pin "104") (pinfunction "IO_L1N_VREF_1_104") (pintype "bidirectional"))
      (node (ref "U3") (pin "18") (pinfunction "D4_18") (pintype "bidirectional"))
    )
    (net (code "107") (name "/XD5") (class "Default")
      (node (ref "U1") (pin "102") (pinfunction "IO_L32P_1_102") (pintype "bidirectional"))
      (node (ref "U3") (pin "19") (pinfunction "D5_19") (pintype "bidirectional"))
    )
    (net (code "108") (name "/XD6") (class "Default")
      (node (ref "U1") (pin "101") (pinfunction "IO_L32N_1_101") (pintype "bidirectional"))
      (node (ref "U3") (pin "20") (pinfunction "D6_20") (pintype "bidirectional"))
    )
    (net (code "109") (name "/XD7") (class "Default")
      (node (ref "U1") (pin "100") (pinfunction "IO_L33P_1_100") (pintype "bidirectional"))
      (node (ref "U3") (pin "21") (pinfunction "D7_21") (pintype "bidirectional"))
    )
    (net (code "110") (name "1.2V") (class "Default")
      (node (ref "C10") (pin "1") (pinfunction "1_1") (pintype "passive"))
      (node (ref "C11") (pin "1") (pinfunction "1_1") (pintype "passive"))
      (node (ref "C12") (pin "1") (pinfunction "1_1") (pintype "passive"))
      (node (ref "C21") (pin "1") (pinfunction "1_1") (pintype "passive"))
      (node (ref "C9") (pin "1") (pinfunction "1_1") (pintype "passive"))
      (node (ref "L2") (pin "2") (pinfunction "2_2") (pintype "passive"))
      (node (ref "U1") (pin "128") (pinfunction "VCCINT_128") (pintype "passive"))
      (node (ref "U1") (pin "19") (pinfunction "VCCINT_19") (pintype "passive"))
      (node (ref "U1") (pin "28") (pinfunction "VCCINT_28") (pintype "passive"))
      (node (ref "U1") (pin "52") (pinfunction "VCCINT_52") (pintype "passive"))
      (node (ref "U1") (pin "89") (pinfunction "VCCINT_89") (pintype "passive"))
    )
    (net (code "111") (name "3.3V") (class "Default")
      (node (ref "C20") (pin "1") (pinfunction "1_1") (pintype "passive"))
      (node (ref "C22") (pin "1") (pinfunction "1_1") (pintype "passive"))
      (node (ref "C23") (pin "1") (pinfunction "1_1") (pintype "passive"))
      (node (ref "C24") (pin "1") (pinfunction "1_1") (pintype "passive"))
      (node (ref "C25") (pin "1") (pinfunction "1_1") (pintype "passive"))
      (node (ref "C26") (pin "1") (pinfunction "1_1") (pintype "passive"))
      (node (ref "C27") (pin "1") (pinfunction "1_1") (pintype "passive"))
      (node (ref "C28") (pin "1") (pinfunction "1_1") (pintype "passive"))
      (node (ref "C29") (pin "1") (pinfunction "1_1") (pintype "passive"))
      (node (ref "C30") (pin "1") (pinfunction "1_1") (pintype "passive"))
      (node (ref "C31") (pin "1") (pinfunction "1_1") (pintype "passive"))
      (node (ref "C32") (pin "1") (pinfunction "1_1") (pintype "passive"))
      (node (ref "C35") (pin "1") (pinfunction "1_1") (pintype "passive"))
      (node (ref "C36") (pin "1") (pinfunction "1_1") (pintype "passive"))
      (node (ref "J2") (pin "4") (pinfunction "4_4") (pintype "passive"))
      (node (ref "J5") (pin "2") (pinfunction "2_2") (pintype "passive"))
      (node (ref "J9") (pin "1") (pinfunction "1_1") (pintype "passive"))
      (node (ref "L1") (pin "2") (pinfunction "2_2") (pintype "passive"))
      (node (ref "R10") (pin "2") (pinfunction "2_2") (pintype "passive"))
      (node (ref "R23") (pin "2") (pinfunction "2_2") (pintype "passive"))
      (node (ref "R24") (pin "2") (pinfunction "2_2") (pintype "passive"))
      (node (ref "R25") (pin "2") (pinfunction "2_2") (pintype "passive"))
      (node (ref "R26") (pin "2") (pinfunction "2_2") (pintype "passive"))
      (node (ref "R27") (pin "1") (pinfunction "1_1") (pintype "passive"))
      (node (ref "R34") (pin "2") (pinfunction "2_2") (pintype "passive"))
      (node (ref "U1") (pin "103") (pinfunction "VCCO_1_103") (pintype "passive"))
      (node (ref "U1") (pin "122") (pinfunction "VCCO_0_122") (pintype "passive"))
      (node (ref "U1") (pin "125") (pinfunction "VCCO_0_125") (pintype "passive"))
      (node (ref "U1") (pin "129") (pinfunction "VCCAUX_129") (pintype "passive"))
      (node (ref "U1") (pin "135") (pinfunction "VCCO_0_135") (pintype "passive"))
      (node (ref "U1") (pin "18") (pinfunction "VCCO_3_18") (pintype "passive"))
      (node (ref "U1") (pin "20") (pinfunction "VCCAUX_20") (pintype "passive"))
      (node (ref "U1") (pin "31") (pinfunction "VCCO_3_31") (pintype "passive"))
      (node (ref "U1") (pin "36") (pinfunction "VCCAUX_36") (pintype "passive"))
      (node (ref "U1") (pin "4") (pinfunction "VCCO_3_4") (pintype "passive"))
      (node (ref "U1") (pin "42") (pinfunction "VCCO_2_42") (pintype "passive"))
      (node (ref "U1") (pin "53") (pinfunction "VCCAUX_53") (pintype "passive"))
      (node (ref "U1") (pin "63") (pinfunction "VCCO_2_63") (pintype "passive"))
      (node (ref "U1") (pin "69") (pinfunction "IO_L1N_M0_CMPMISO_2_69") (pintype "bidirectional"))
      (node (ref "U1") (pin "76") (pinfunction "VCCO_1_76") (pintype "passive"))
      (node (ref "U1") (pin "86") (pinfunction "VCCO_1_86") (pintype "passive"))
      (node (ref "U1") (pin "90") (pinfunction "VCCAUX_90") (pintype "passive"))
      (node (ref "U2") (pin "8") (pinfunction "VCC_8") (pintype "power_in"))
      (node (ref "U3") (pin "32") (pinfunction "VCC_32") (pintype "power_in"))
      (node (ref "U5") (pin "4") (pinfunction "VDD_4") (pintype "power_in"))
    )
    (net (code "112") (name "5V") (class "Default")
      (node (ref "C14") (pin "1") (pinfunction "1_1") (pintype "passive"))
      (node (ref "C18") (pin "1") (pinfunction "1_1") (pintype "passive"))
      (node (ref "C33") (pin "1") (pinfunction "1_1") (pintype "passive"))
      (node (ref "C34") (pin "1") (pinfunction "1_1") (pintype "passive"))
      (node (ref "J5") (pin "1") (pinfunction "1_1") (pintype "passive"))
      (node (ref "J6") (pin "1") (pinfunction "1_1") (pintype "passive"))
      (node (ref "J7") (pin "1") (pinfunction "1_1") (pintype "passive"))
      (node (ref "J8") (pin "1") (pinfunction "1_1") (pintype "passive"))
      (node (ref "L3") (pin "2") (pinfunction "2_2") (pintype "passive"))
      (node (ref "R30") (pin "2") (pinfunction "2_2") (pintype "passive"))
      (node (ref "R6") (pin "1") (pinfunction "1_1") (pintype "passive"))
      (node (ref "U4") (pin "14") (pinfunction "DPOS_14") (pintype "input"))
      (node (ref "U4") (pin "15") (pinfunction "VSYNC_15") (pintype "input"))
      (node (ref "U4") (pin "4") (pinfunction "APOS_4") (pintype "input"))
      (node (ref "U4") (pin "5") (pinfunction "ENCD_5") (pintype "input"))
      (node (ref "U6") (pin "3") (pinfunction "VIN_3") (pintype "power_in"))
      (node (ref "U7") (pin "3") (pinfunction "VIN_3") (pintype "power_in"))
    )
    (net (code "113") (name "GND") (class "Default")
      (node (ref "C1") (pin "2") (pinfunction "2_2") (pintype "passive"))
      (node (ref "C10") (pin "2") (pinfunction "2_2") (pintype "passive"))
      (node (ref "C11") (pin "2") (pinfunction "2_2") (pintype "passive"))
      (node (ref "C12") (pin "2") (pinfunction "2_2") (pintype "passive"))
      (node (ref "C14") (pin "2") (pinfunction "2_2") (pintype "passive"))
      (node (ref "C15") (pin "2") (pinfunction "2_2") (pintype "passive"))
      (node (ref "C18") (pin "2") (pinfunction "2_2") (pintype "passive"))
      (node (ref "C19") (pin "2") (pinfunction "2_2") (pintype "passive"))
      (node (ref "C2") (pin "1") (pinfunction "1_1") (pintype "passive"))
      (node (ref "C20") (pin "2") (pinfunction "2_2") (pintype "passive"))
      (node (ref "C21") (pin "2") (pinfunction "2_2") (pintype "passive"))
      (node (ref "C22") (pin "2") (pinfunction "2_2") (pintype "passive"))
      (node (ref "C23") (pin "2") (pinfunction "2_2") (pintype "passive"))
      (node (ref "C24") (pin "2") (pinfunction "2_2") (pintype "passive"))
      (node (ref "C25") (pin "2") (pinfunction "2_2") (pintype "passive"))
      (node (ref "C26") (pin "2") (pinfunction "2_2") (pintype "passive"))
      (node (ref "C27") (pin "2") (pinfunction "2_2") (pintype "passive"))
      (node (ref "C28") (pin "2") (pinfunction "2_2") (pintype "passive"))
      (node (ref "C29") (pin "2") (pinfunction "2_2") (pintype "passive"))
      (node (ref "C3") (pin "1") (pinfunction "1_1") (pintype "passive"))
      (node (ref "C30") (pin "2") (pinfunction "2_2") (pintype "passive"))
      (node (ref "C31") (pin "2") (pinfunction "2_2") (pintype "passive"))
      (node (ref "C32") (pin "2") (pinfunction "2_2") (pintype "passive"))
      (node (ref "C33") (pin "2") (pinfunction "2_2") (pintype "passive"))
      (node (ref "C34") (pin "2") (pinfunction "2_2") (pintype "passive"))
      (node (ref "C35") (pin "2") (pinfunction "2_2") (pintype "passive"))
      (node (ref "C36") (pin "2") (pinfunction "2_2") (pintype "passive"))
      (node (ref "C4") (pin "1") (pinfunction "1_1") (pintype "passive"))
      (node (ref "C9") (pin "2") (pinfunction "2_2") (pintype "passive"))
      (node (ref "D1") (pin "1") (pinfunction "A_1") (pintype "passive"))
      (node (ref "D2") (pin "2") (pinfunction "CATHODE_2") (pintype "passive"))
      (node (ref "J1") (pin "5") (pinfunction "5_5") (pintype "passive"))
      (node (ref "J2") (pin "6") (pinfunction "6_6") (pintype "passive"))
      (node (ref "J3") (pin "1") (pinfunction "S_1") (pintype "power_in"))
      (node (ref "J4") (pin "4") (pinfunction "R_4") (pintype "passive"))
      (node (ref "J5") (pin "40") (pinfunction "40_40") (pintype "passive"))
      (node (ref "J6") (pin "9") (pinfunction "9_9") (pintype "passive"))
      (node (ref "J7") (pin "4") (pinfunction "4_4") (pintype "passive"))
      (node (ref "J8") (pin "3") (pinfunction "3_3") (pintype "passive"))
      (node (ref "J9") (pin "2") (pinfunction "2_2") (pintype "passive"))
      (node (ref "Q1") (pin "3") (pinfunction "EMITTER_3") (pintype "passive"))
      (node (ref "R1") (pin "2") (pinfunction "2_2") (pintype "passive"))
      (node (ref "R2") (pin "2") (pinfunction "2_2") (pintype "passive"))
      (node (ref "R29") (pin "2") (pinfunction "2_2") (pintype "passive"))
      (node (ref "R3") (pin "2") (pinfunction "2_2") (pintype "passive"))
      (node (ref "R31") (pin "2") (pinfunction "2_2") (pintype "passive"))
      (node (ref "U1") (pin "108") (pinfunction "GND_108") (pintype "power_in"))
      (node (ref "U1") (pin "113") (pinfunction "GND_113") (pintype "power_in"))
      (node (ref "U1") (pin "13") (pinfunction "GND_13") (pintype "passive"))
      (node (ref "U1") (pin "130") (pinfunction "GND_130") (pintype "passive"))
      (node (ref "U1") (pin "136") (pinfunction "GND_136") (pintype "passive"))
      (node (ref "U1") (pin "144") (pinfunction "IO_L1P_HSWAPEN_0_144") (pintype "bidirectional"))
      (node (ref "U1") (pin "25") (pinfunction "GND_25") (pintype "passive"))
      (node (ref "U1") (pin "3") (pinfunction "GND_3") (pintype "passive"))
      (node (ref "U1") (pin "49") (pinfunction "GND_49") (pintype "passive"))
      (node (ref "U1") (pin "54") (pinfunction "GND_54") (pintype "passive"))
      (node (ref "U1") (pin "60") (pinfunction "IO_L13P_M1_2_60") (pintype "bidirectional"))
      (node (ref "U1") (pin "68") (pinfunction "GND_68") (pintype "passive"))
      (node (ref "U1") (pin "73") (pinfunction "SUSPEND_73") (pintype "passive"))
      (node (ref "U1") (pin "77") (pinfunction "GND_77") (pintype "power_in"))
      (node (ref "U1") (pin "91") (pinfunction "GND_91") (pintype "power_in"))
      (node (ref "U1") (pin "96") (pinfunction "GND_96") (pintype "power_in"))
      (node (ref "U2") (pin "4") (pinfunction "GND_4") (pintype "power_in"))
      (node (ref "U3") (pin "16") (pinfunction "GND_16") (pintype "power_in"))
      (node (ref "U3") (pin "22") (pinfunction "~{CE1}_22") (pintype "input"))
      (node (ref "U3") (pin "24") (pinfunction "~{OE}_24") (pintype "input"))
      (node (ref "U4") (pin "12") (pinfunction "SELECT_12") (pintype "input"))
      (node (ref "U4") (pin "13") (pinfunction "DGND_13") (pintype "input"))
      (node (ref "U4") (pin "2") (pinfunction "AGND_2") (pintype "input"))
      (node (ref "U5") (pin "2") (pinfunction "VSS_2") (pintype "passive"))
      (node (ref "U6") (pin "1") (pinfunction "GND_1") (pintype "power_in"))
      (node (ref "U7") (pin "1") (pinfunction "GND_1") (pintype "power_in"))
      (node (ref "Y2") (pin "2") (pinfunction "2_2") (pintype "passive"))
    )
    (net (code "114") (name "Net-(C5-Pad1)") (class "Default")
      (node (ref "C5") (pin "1") (pinfunction "1_1") (pintype "passive"))
      (node (ref "R11") (pin "2") (pinfunction "2_2") (pintype "passive"))
    )
    (net (code "115") (name "Net-(C13-Pad2)") (class "Default")
      (node (ref "C13") (pin "2") (pinfunction "2_2") (pintype "passive"))
      (node (ref "R4") (pin "1") (pinfunction "1_1") (pintype "passive"))
    )
    (net (code "116") (name "Net-(D1-K)") (class "Default")
      (node (ref "C2") (pin "2") (pinfunction "2_2") (pintype "passive"))
      (node (ref "C5") (pin "2") (pinfunction "2_2") (pintype "passive"))
      (node (ref "D1") (pin "2") (pinfunction "K_2") (pintype "passive"))
      (node (ref "R28") (pin "1") (pinfunction "1_1") (pintype "passive"))
    )
    (net (code "117") (name "Net-(D2-ANODE)") (class "Default")
      (node (ref "D2") (pin "1") (pinfunction "ANODE_1") (pintype "passive"))
      (node (ref "R6") (pin "2") (pinfunction "2_2") (pintype "passive"))
    )
    (net (code "118") (name "Net-(J1-Pad1)") (class "Default")
      (node (ref "J1") (pin "1") (pinfunction "1_1") (pintype "passive"))
      (node (ref "L3") (pin "1") (pinfunction "1_1") (pintype "passive"))
    )
    (net (code "119") (name "Net-(J3-T)") (class "Default")
      (node (ref "J3") (pin "2") (pinfunction "T_2") (pintype "passive"))
      (node (ref "R11") (pin "1") (pinfunction "1_1") (pintype "passive"))
      (node (ref "R29") (pin "1") (pinfunction "1_1") (pintype "passive"))
    )
    (net (code "120") (name "Net-(J7-Pad2)") (class "Default")
      (node (ref "J7") (pin "2") (pinfunction "2_2") (pintype "passive"))
      (node (ref "R8") (pin "1") (pinfunction "1_1") (pintype "passive"))
    )
    (net (code "121") (name "Net-(J7-Pad3)") (class "Default")
      (node (ref "J7") (pin "3") (pinfunction "3_3") (pintype "passive"))
      (node (ref "R9") (pin "1") (pinfunction "1_1") (pintype "passive"))
    )
    (net (code "122") (name "Net-(Q1-BASE)") (class "Default")
      (node (ref "Q1") (pin "2") (pinfunction "BASE_2") (pintype "input"))
      (node (ref "R28") (pin "2") (pinfunction "2_2") (pintype "passive"))
    )
    (net (code "123") (name "Net-(U1-DONE_2)") (class "Default")
      (node (ref "R10") (pin "1") (pinfunction "1_1") (pintype "passive"))
      (node (ref "U1") (pin "71") (pinfunction "DONE_2_71") (pintype "passive"))
    )
    (net (code "124") (name "Net-(U1-IO_L65P_INIT_B_2)") (class "Default")
      (node (ref "R23") (pin "1") (pinfunction "1_1") (pintype "passive"))
      (node (ref "U1") (pin "39") (pinfunction "IO_L65P_INIT_B_2_39") (pintype "bidirectional"))
    )
    (net (code "125") (name "Net-(U1-PROGRAM_B_2)") (class "Default")
      (node (ref "R24") (pin "1") (pinfunction "1_1") (pintype "passive"))
      (node (ref "U1") (pin "37") (pinfunction "PROGRAM_B_2_37") (pintype "passive"))
    )
    (net (code "126") (name "Net-(U4-BIN)") (class "Default")
      (node (ref "C6") (pin "2") (pinfunction "2_2") (pintype "passive"))
      (node (ref "U4") (pin "8") (pinfunction "BIN_8") (pintype "input"))
    )
    (net (code "127") (name "Net-(U4-CMPS)") (class "Default")
      (node (ref "C13") (pin "1") (pinfunction "1_1") (pintype "passive"))
      (node (ref "U4") (pin "10") (pinfunction "CMPS_10") (pintype "output"))
    )
    (net (code "128") (name "Net-(U4-FIN)") (class "Default")
      (node (ref "C1") (pin "1") (pinfunction "1_1") (pintype "passive"))
      (node (ref "U4") (pin "3") (pinfunction "FIN_3") (pintype "input"))
      (node (ref "Y2") (pin "1") (pinfunction "1_1") (pintype "passive"))
    )
    (net (code "129") (name "Net-(U4-GIN)") (class "Default")
      (node (ref "C7") (pin "2") (pinfunction "2_2") (pintype "passive"))
      (node (ref "U4") (pin "7") (pinfunction "GIN_7") (pintype "input"))
    )
    (net (code "130") (name "Net-(U4-RIN)") (class "Default")
      (node (ref "C8") (pin "2") (pinfunction "2_2") (pintype "passive"))
      (node (ref "U4") (pin "6") (pinfunction "RIN_6") (pintype "input"))
    )
    (net (code "131") (name "Net-(U6-TAB)") (class "Default")
      (node (ref "C15") (pin "1") (pinfunction "1_1") (pintype "passive"))
      (node (ref "L1") (pin "1") (pinfunction "1_1") (pintype "passive"))
      (node (ref "U6") (pin "2") (pinfunction "VOUT_2") (pintype "power_in"))
      (node (ref "U6") (pin "4") (pinfunction "TAB_4") (pintype "passive"))
    )
    (net (code "132") (name "Net-(U7-TAB)") (class "Default")
      (node (ref "C19") (pin "1") (pinfunction "1_1") (pintype "passive"))
      (node (ref "L2") (pin "1") (pinfunction "1_1") (pintype "passive"))
      (node (ref "U7") (pin "2") (pinfunction "VOUT_2") (pintype "power_in"))
      (node (ref "U7") (pin "4") (pinfunction "TAB_4") (pintype "passive"))
    )
    (net (code "133") (name "unconnected-(J2-Pad1)") (class "Default")
      (node (ref "J2") (pin "1") (pinfunction "1_1") (pintype "passive"))
    )
    (net (code "134") (name "unconnected-(J2-Pad8)") (class "Default")
      (node (ref "J2") (pin "8") (pinfunction "8_8") (pintype "passive"))
    )
    (net (code "135") (name "unconnected-(J3-TN-Pad3)") (class "Default")
      (node (ref "J3") (pin "3") (pinfunction "TN_3") (pintype "passive"))
    )
    (net (code "136") (name "unconnected-(J8-Pad5)") (class "Default")
      (node (ref "J8") (pin "5") (pinfunction "5_5") (pintype "passive"))
    )
    (net (code "137") (name "unconnected-(U1-CMPCS_B_2-Pad72)") (class "Default")
      (node (ref "U1") (pin "72") (pinfunction "CMPCS_B_2_72") (pintype "passive"))
    )
    (net (code "138") (name "unconnected-(U4-CRMA-Pad9)") (class "Default")
      (node (ref "U4") (pin "9") (pinfunction "CRMA_9") (pintype "output"))
    )
    (net (code "139") (name "unconnected-(U4-LUMA-Pad11)") (class "Default")
      (node (ref "U4") (pin "11") (pinfunction "LUMA_11") (pintype "output"))
    )
    (net (code "140") (name "unconnected-(U5-E{slash}D-Pad1)") (class "Default")
      (node (ref "U5") (pin "1") (pinfunction "E/D_1") (pintype "output"))
    )
  )
)
